# RF_125KHz.net
KiCad netlist of a schematic drawn in Altium Designer
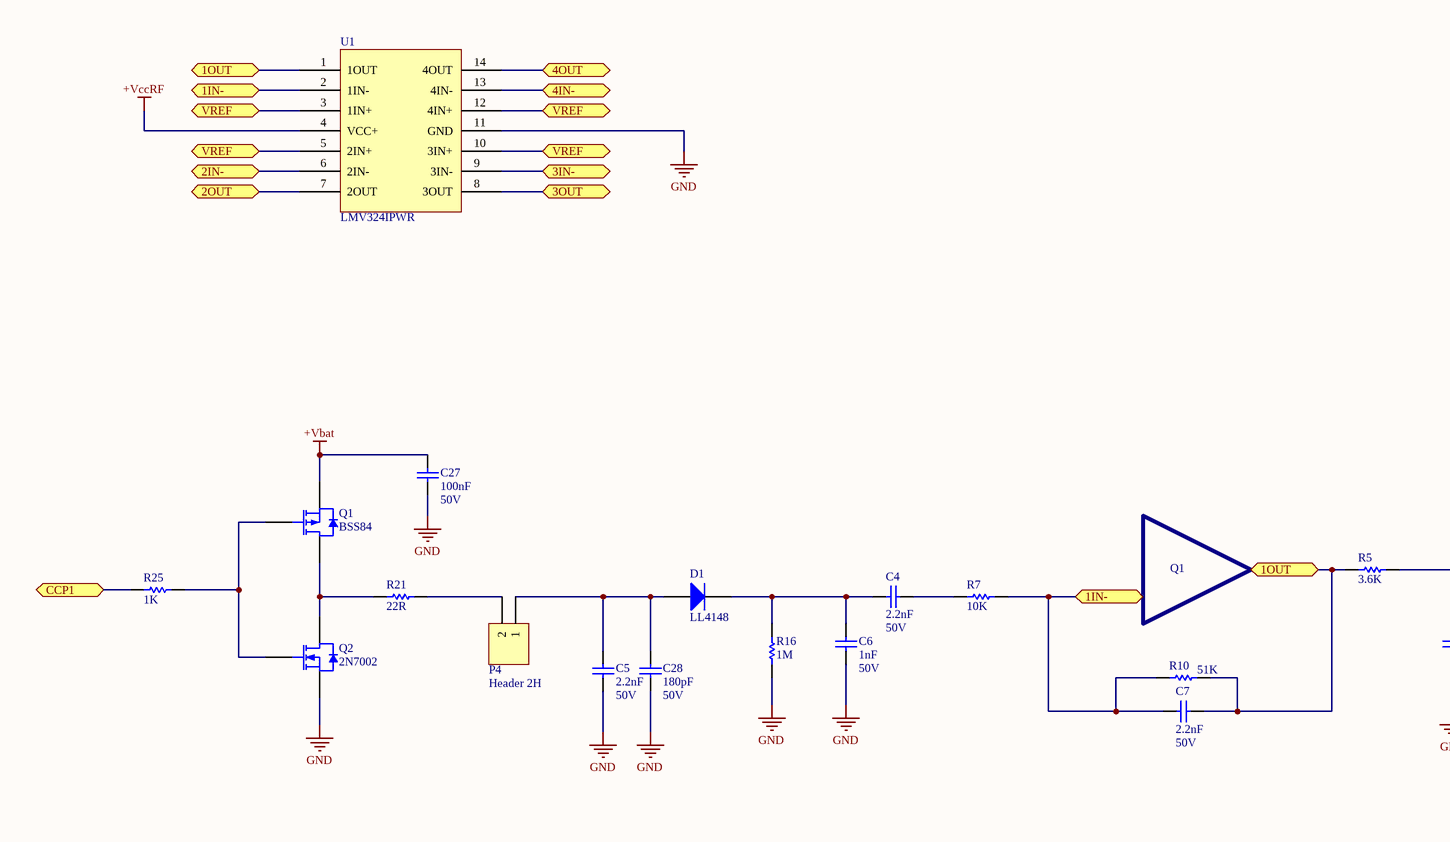
[diagram p0: RF_125KHz.SchDoc, left]
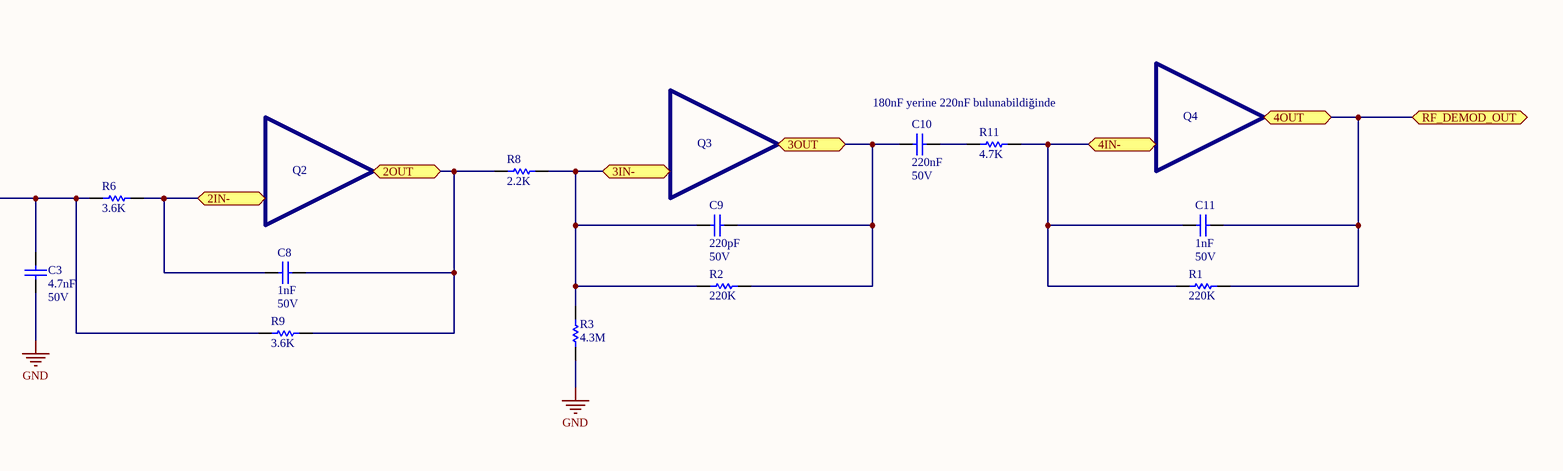
[diagram p1: RF_125KHz.SchDoc, right]

(export (version "E")
  (design (tool "Eeschema 10.0.6"))
  (components
    (comp (ref "C3")
      (value "4.7nF")
      (footprint "6-0805_N")
      (description "Capacitor")
      (fields
        (field (name "VOLTAGE") "50V")
        (field (name "Comment") "Cap")
        (field (name "PUBLISHER") "Altium Limited")
      )
      (libsource (lib "Erdem_05112012") (part "Cap"))
    )
    (comp (ref "C4")
      (value "2.2nF")
      (footprint "6-0805_N")
      (description "Capacitor")
      (fields
        (field (name "VOLTAGE") "50V")
        (field (name "Comment") "Cap")
        (field (name "PUBLISHER") "Altium Limited")
      )
      (libsource (lib "Erdem_05112012") (part "Cap"))
    )
    (comp (ref "C5")
      (value "2.2nF")
      (footprint "6-0805_N")
      (description "Capacitor")
      (fields
        (field (name "VOLTAGE") "50V")
        (field (name "Comment") "Cap")
        (field (name "PUBLISHER") "Altium Limited")
      )
      (libsource (lib "Erdem_05112012") (part "Cap"))
    )
    (comp (ref "C6")
      (value "1nF")
      (footprint "6-0805_N")
      (description "Capacitor")
      (fields
        (field (name "VOLTAGE") "50V")
        (field (name "Comment") "Cap")
        (field (name "PUBLISHER") "Altium Limited")
      )
      (libsource (lib "Erdem_05112012") (part "Cap"))
    )
    (comp (ref "C7")
      (value "2.2nF")
      (footprint "6-0805_N")
      (description "Capacitor")
      (fields
        (field (name "VOLTAGE") "50V")
        (field (name "Comment") "Cap")
        (field (name "PUBLISHER") "Altium Limited")
      )
      (libsource (lib "Erdem_05112012") (part "Cap"))
    )
    (comp (ref "C8")
      (value "1nF")
      (footprint "6-0805_N")
      (description "Capacitor")
      (fields
        (field (name "VOLTAGE") "50V")
        (field (name "Comment") "Cap")
        (field (name "PUBLISHER") "Altium Limited")
      )
      (libsource (lib "Erdem_05112012") (part "Cap"))
    )
    (comp (ref "C9")
      (value "220pF")
      (footprint "6-0805_N")
      (description "Capacitor")
      (fields
        (field (name "VOLTAGE") "50V")
        (field (name "Comment") "Cap")
        (field (name "PUBLISHER") "Altium Limited")
      )
      (libsource (lib "Erdem_05112012") (part "Cap"))
    )
    (comp (ref "C10")
      (value "220nF")
      (footprint "6-0805_N")
      (description "Capacitor")
      (fields
        (field (name "VOLTAGE") "50V")
        (field (name "Comment") "Cap")
        (field (name "PUBLISHER") "Altium Limited")
      )
      (libsource (lib "Erdem_05112012") (part "Cap"))
    )
    (comp (ref "C11")
      (value "1nF")
      (footprint "6-0805_N")
      (description "Capacitor")
      (fields
        (field (name "VOLTAGE") "50V")
        (field (name "Comment") "Cap")
        (field (name "PUBLISHER") "Altium Limited")
      )
      (libsource (lib "Erdem_05112012") (part "Cap"))
    )
    (comp (ref "C27")
      (value "100nF")
      (footprint "3-0603_N")
      (description "Capacitor")
      (fields
        (field (name "VOLTAGE") "50V")
        (field (name "Comment") "Cap")
        (field (name "PUBLISHER") "Altium Limited")
      )
      (libsource (lib "Erdem_05112012") (part "Cap"))
    )
    (comp (ref "C28")
      (value "180pF")
      (footprint "6-0805_N")
      (description "Capacitor")
      (fields
        (field (name "VOLTAGE") "50V")
        (field (name "Comment") "Cap")
        (field (name "PUBLISHER") "Altium Limited")
      )
      (libsource (lib "Erdem_05112012") (part "Cap"))
    )
    (comp (ref "D1")
      (value "LL4148")
      (footprint "DL-35 - S")
      (description "1 Amp General Purpose Rectifier")
      (fields (field (name "PUBLISHER") "Altium Limited"))
      (libsource (lib "Erdem_05112012") (part "LL4148"))
    )
    (comp (ref "P4")
      (value "Header 2H")
      (footprint "HDR1X2H-180 derece")
      (description "Header, 2-Pin, Right Angle")
      (fields (field (name "PUBLISHER") "Altium Limited"))
      (libsource (lib "Erdem_05112012") (part "Header 2H"))
    )
    (comp (ref "Q1")
      (value "BSS84")
      (footprint "SOT23_N")
      (description "P-channel Enhancement Mode Vertical D-MOSFET")
      (fields (field (name "PUBLISHER") "Altium Limited"))
      (libsource (lib "Erdem_05112012") (part "BSS84"))
    )
    (comp (ref "Q2")
      (value "2N7002")
      (footprint "SOT23_N")
      (description "N-channel Enhancement Mode Field-effect Transistor")
      (fields (field (name "PUBLISHER") "Altium Limited"))
      (libsource (lib "Erdem_05112012") (part "2N7002"))
    )
    (comp (ref "R1")
      (value "220K")
      (footprint "6-0805_N")
      (description "Resistor")
      (fields (field (name "Comment") "Res1") (field (name "PUBLISHER") "Altium Limited"))
      (libsource (lib "Erdem_05112012") (part "Res1"))
    )
    (comp (ref "R2")
      (value "220K")
      (footprint "6-0805_N")
      (description "Resistor")
      (fields (field (name "Comment") "Res1") (field (name "PUBLISHER") "Altium Limited"))
      (libsource (lib "Erdem_05112012") (part "Res1"))
    )
    (comp (ref "R3")
      (value "4.3M")
      (footprint "6-0805_N")
      (description "Resistor")
      (fields (field (name "Comment") "Res1") (field (name "PUBLISHER") "Altium Limited"))
      (libsource (lib "Erdem_05112012") (part "Res1"))
    )
    (comp (ref "R5")
      (value "3.6K")
      (footprint "6-0805_N")
      (description "Resistor")
      (fields (field (name "Comment") "Res1") (field (name "PUBLISHER") "Altium Limited"))
      (libsource (lib "Erdem_05112012") (part "Res1"))
    )
    (comp (ref "R6")
      (value "3.6K")
      (footprint "6-0805_N")
      (description "Resistor")
      (fields (field (name "Comment") "Res1") (field (name "PUBLISHER") "Altium Limited"))
      (libsource (lib "Erdem_05112012") (part "Res1"))
    )
    (comp (ref "R7")
      (value "10K")
      (footprint "6-0805_N")
      (description "Resistor")
      (fields (field (name "Comment") "Res1") (field (name "PUBLISHER") "Altium Limited"))
      (libsource (lib "Erdem_05112012") (part "Res1"))
    )
    (comp (ref "R8")
      (value "2.2K")
      (footprint "6-0805_N")
      (description "Resistor")
      (fields (field (name "Comment") "Res1") (field (name "PUBLISHER") "Altium Limited"))
      (libsource (lib "Erdem_05112012") (part "Res1"))
    )
    (comp (ref "R9")
      (value "3.6K")
      (footprint "6-0805_N")
      (description "Resistor")
      (fields (field (name "Comment") "Res1") (field (name "PUBLISHER") "Altium Limited"))
      (libsource (lib "Erdem_05112012") (part "Res1"))
    )
    (comp (ref "R10")
      (value "51K")
      (footprint "6-0805_N")
      (description "Resistor")
      (fields (field (name "Comment") "Res1") (field (name "PUBLISHER") "Altium Limited"))
      (libsource (lib "Erdem_05112012") (part "Res1"))
    )
    (comp (ref "R11")
      (value "4.7K")
      (footprint "6-0805_N")
      (description "Resistor")
      (fields (field (name "Comment") "Res1") (field (name "PUBLISHER") "Altium Limited"))
      (libsource (lib "Erdem_05112012") (part "Res1"))
    )
    (comp (ref "R16")
      (value "1M")
      (footprint "6-0805_N")
      (description "Resistor")
      (fields (field (name "Comment") "Res1") (field (name "PUBLISHER") "Altium Limited"))
      (libsource (lib "Erdem_05112012") (part "Res1"))
    )
    (comp (ref "R21")
      (value "22R")
      (footprint "6-0805_N")
      (description "Resistor")
      (fields (field (name "Comment") "Res1") (field (name "PUBLISHER") "Altium Limited"))
      (libsource (lib "Erdem_05112012") (part "Res1"))
    )
    (comp (ref "R25")
      (value "1K")
      (footprint "3-0603_N")
      (description "Resistor")
      (fields (field (name "Comment") "Res1") (field (name "PUBLISHER") "Altium Limited"))
      (libsource (lib "Erdem_05112012") (part "Res1"))
    )
    (comp (ref "U1")
      (value "LMV324IPWR")
      (footprint "TSSOP-14N")
      (description "IC OPAMP GP R-R 1MHZ 14TSSOP")
      (fields
        (field (name "DIGI-KEY PART NUMBER") "296-9570-2-ND")
        (field (name "MANUFACTURER") "Texas Instruments")
      )
      (libsource (lib "Erdem_05112012") (part "LMV324IPWR"))
    )
  )
  (nets
    (net (code "1") (name "+Vbat") (class "Default")
      (node (ref "C27") (pin "2") (pinfunction "2_2") (pintype "passive"))
      (node (ref "Q1") (pin "2") (pinfunction "S_2") (pintype "passive"))
    )
    (net (code "2") (name "+VccRF") (class "Default")
      (node (ref "U1") (pin "4") (pinfunction "VCC+_4") (pintype "passive"))
    )
    (net (code "3") (name "/1IN-") (class "Default")
      (node (ref "C7") (pin "1") (pinfunction "1_1") (pintype "passive"))
      (node (ref "R10") (pin "2") (pinfunction "2_2") (pintype "passive"))
      (node (ref "R7") (pin "1") (pinfunction "1_1") (pintype "passive"))
      (node (ref "U1") (pin "2") (pinfunction "1IN-_2") (pintype "passive"))
    )
    (net (code "4") (name "/1OUT") (class "Default")
      (node (ref "C7") (pin "2") (pinfunction "2_2") (pintype "passive"))
      (node (ref "R10") (pin "1") (pinfunction "1_1") (pintype "passive"))
      (node (ref "R5") (pin "2") (pinfunction "2_2") (pintype "passive"))
      (node (ref "U1") (pin "1") (pinfunction "1OUT_1") (pintype "passive"))
    )
    (net (code "5") (name "/2IN-") (class "Default")
      (node (ref "C8") (pin "1") (pinfunction "1_1") (pintype "passive"))
      (node (ref "R6") (pin "1") (pinfunction "1_1") (pintype "passive"))
      (node (ref "U1") (pin "6") (pinfunction "2IN-_6") (pintype "passive"))
    )
    (net (code "6") (name "/2OUT") (class "Default")
      (node (ref "C8") (pin "2") (pinfunction "2_2") (pintype "passive"))
      (node (ref "R8") (pin "2") (pinfunction "2_2") (pintype "passive"))
      (node (ref "R9") (pin "1") (pinfunction "1_1") (pintype "passive"))
      (node (ref "U1") (pin "7") (pinfunction "2OUT_7") (pintype "passive"))
    )
    (net (code "7") (name "/3IN-") (class "Default")
      (node (ref "C9") (pin "1") (pinfunction "1_1") (pintype "passive"))
      (node (ref "R2") (pin "2") (pinfunction "2_2") (pintype "passive"))
      (node (ref "R3") (pin "1") (pinfunction "1_1") (pintype "passive"))
      (node (ref "R8") (pin "1") (pinfunction "1_1") (pintype "passive"))
      (node (ref "U1") (pin "9") (pinfunction "3IN-_9") (pintype "passive"))
    )
    (net (code "8") (name "/3OUT") (class "Default")
      (node (ref "C10") (pin "1") (pinfunction "1_1") (pintype "passive"))
      (node (ref "C9") (pin "2") (pinfunction "2_2") (pintype "passive"))
      (node (ref "R2") (pin "1") (pinfunction "1_1") (pintype "passive"))
      (node (ref "U1") (pin "8") (pinfunction "3OUT_8") (pintype "passive"))
    )
    (net (code "9") (name "/4IN-") (class "Default")
      (node (ref "C11") (pin "1") (pinfunction "1_1") (pintype "passive"))
      (node (ref "R1") (pin "1") (pinfunction "1_1") (pintype "passive"))
      (node (ref "R11") (pin "2") (pinfunction "2_2") (pintype "passive"))
      (node (ref "U1") (pin "13") (pinfunction "4IN-_13") (pintype "passive"))
    )
    (net (code "10") (name "/4OUT") (class "Default")
      (node (ref "C11") (pin "2") (pinfunction "2_2") (pintype "passive"))
      (node (ref "R1") (pin "2") (pinfunction "2_2") (pintype "passive"))
      (node (ref "U1") (pin "14") (pinfunction "4OUT_14") (pintype "passive"))
    )
    (net (code "11") (name "/CCP1") (class "Default")
      (node (ref "R25") (pin "1") (pinfunction "1_1") (pintype "passive"))
    )
    (net (code "12") (name "/VREF") (class "Default")
      (node (ref "U1") (pin "10") (pinfunction "3IN+_10") (pintype "passive"))
      (node (ref "U1") (pin "12") (pinfunction "4IN+_12") (pintype "passive"))
      (node (ref "U1") (pin "3") (pinfunction "1IN+_3") (pintype "passive"))
      (node (ref "U1") (pin "5") (pinfunction "2IN+_5") (pintype "passive"))
    )
    (net (code "13") (name "GND") (class "Default")
      (node (ref "C27") (pin "1") (pinfunction "1_1") (pintype "passive"))
      (node (ref "C28") (pin "2") (pinfunction "2_2") (pintype "passive"))
      (node (ref "C3") (pin "1") (pinfunction "1_1") (pintype "passive"))
      (node (ref "C5") (pin "2") (pinfunction "2_2") (pintype "passive"))
      (node (ref "C6") (pin "2") (pinfunction "2_2") (pintype "passive"))
      (node (ref "Q2") (pin "2") (pinfunction "S_2") (pintype "passive"))
      (node (ref "R16") (pin "1") (pinfunction "1_1") (pintype "passive"))
      (node (ref "R3") (pin "2") (pinfunction "2_2") (pintype "passive"))
      (node (ref "U1") (pin "11") (pinfunction "GND_11") (pintype "passive"))
    )
    (net (code "14") (name "Net-(C3-Pad2)") (class "Default")
      (node (ref "C3") (pin "2") (pinfunction "2_2") (pintype "passive"))
      (node (ref "R5") (pin "1") (pinfunction "1_1") (pintype "passive"))
      (node (ref "R6") (pin "2") (pinfunction "2_2") (pintype "passive"))
      (node (ref "R9") (pin "2") (pinfunction "2_2") (pintype "passive"))
    )
    (net (code "15") (name "Net-(C4-Pad1)") (class "Default")
      (node (ref "C4") (pin "1") (pinfunction "1_1") (pintype "passive"))
      (node (ref "R7") (pin "2") (pinfunction "2_2") (pintype "passive"))
    )
    (net (code "16") (name "Net-(C10-Pad2)") (class "Default")
      (node (ref "C10") (pin "2") (pinfunction "2_2") (pintype "passive"))
      (node (ref "R11") (pin "1") (pinfunction "1_1") (pintype "passive"))
    )
    (net (code "17") (name "Net-(D1-A)") (class "Default")
      (node (ref "C28") (pin "1") (pinfunction "1_1") (pintype "passive"))
      (node (ref "C5") (pin "1") (pinfunction "1_1") (pintype "passive"))
      (node (ref "D1") (pin "1") (pinfunction "A_1") (pintype "passive"))
      (node (ref "P4") (pin "1") (pinfunction "1_1") (pintype "passive"))
    )
    (net (code "18") (name "Net-(D1-K)") (class "Default")
      (node (ref "C4") (pin "2") (pinfunction "2_2") (pintype "passive"))
      (node (ref "C6") (pin "1") (pinfunction "1_1") (pintype "passive"))
      (node (ref "D1") (pin "2") (pinfunction "K_2") (pintype "passive"))
      (node (ref "R16") (pin "2") (pinfunction "2_2") (pintype "passive"))
    )
    (net (code "19") (name "Net-(P4-Pad2)") (class "Default")
      (node (ref "P4") (pin "2") (pinfunction "2_2") (pintype "passive"))
      (node (ref "R21") (pin "2") (pinfunction "2_2") (pintype "passive"))
    )
    (net (code "20") (name "Net-(Q1-D)") (class "Default")
      (node (ref "Q1") (pin "3") (pinfunction "D_3") (pintype "passive"))
      (node (ref "Q2") (pin "3") (pinfunction "D_3") (pintype "passive"))
      (node (ref "R21") (pin "1") (pinfunction "1_1") (pintype "passive"))
    )
    (net (code "21") (name "Net-(Q1-G)") (class "Default")
      (node (ref "Q1") (pin "1") (pinfunction "G_1") (pintype "passive"))
      (node (ref "Q2") (pin "1") (pinfunction "G_1") (pintype "passive"))
      (node (ref "R25") (pin "2") (pinfunction "2_2") (pintype "passive"))
    )
  )
)
